# NEWNU32.net
KiCad netlist of a schematic drawn in EAGLE
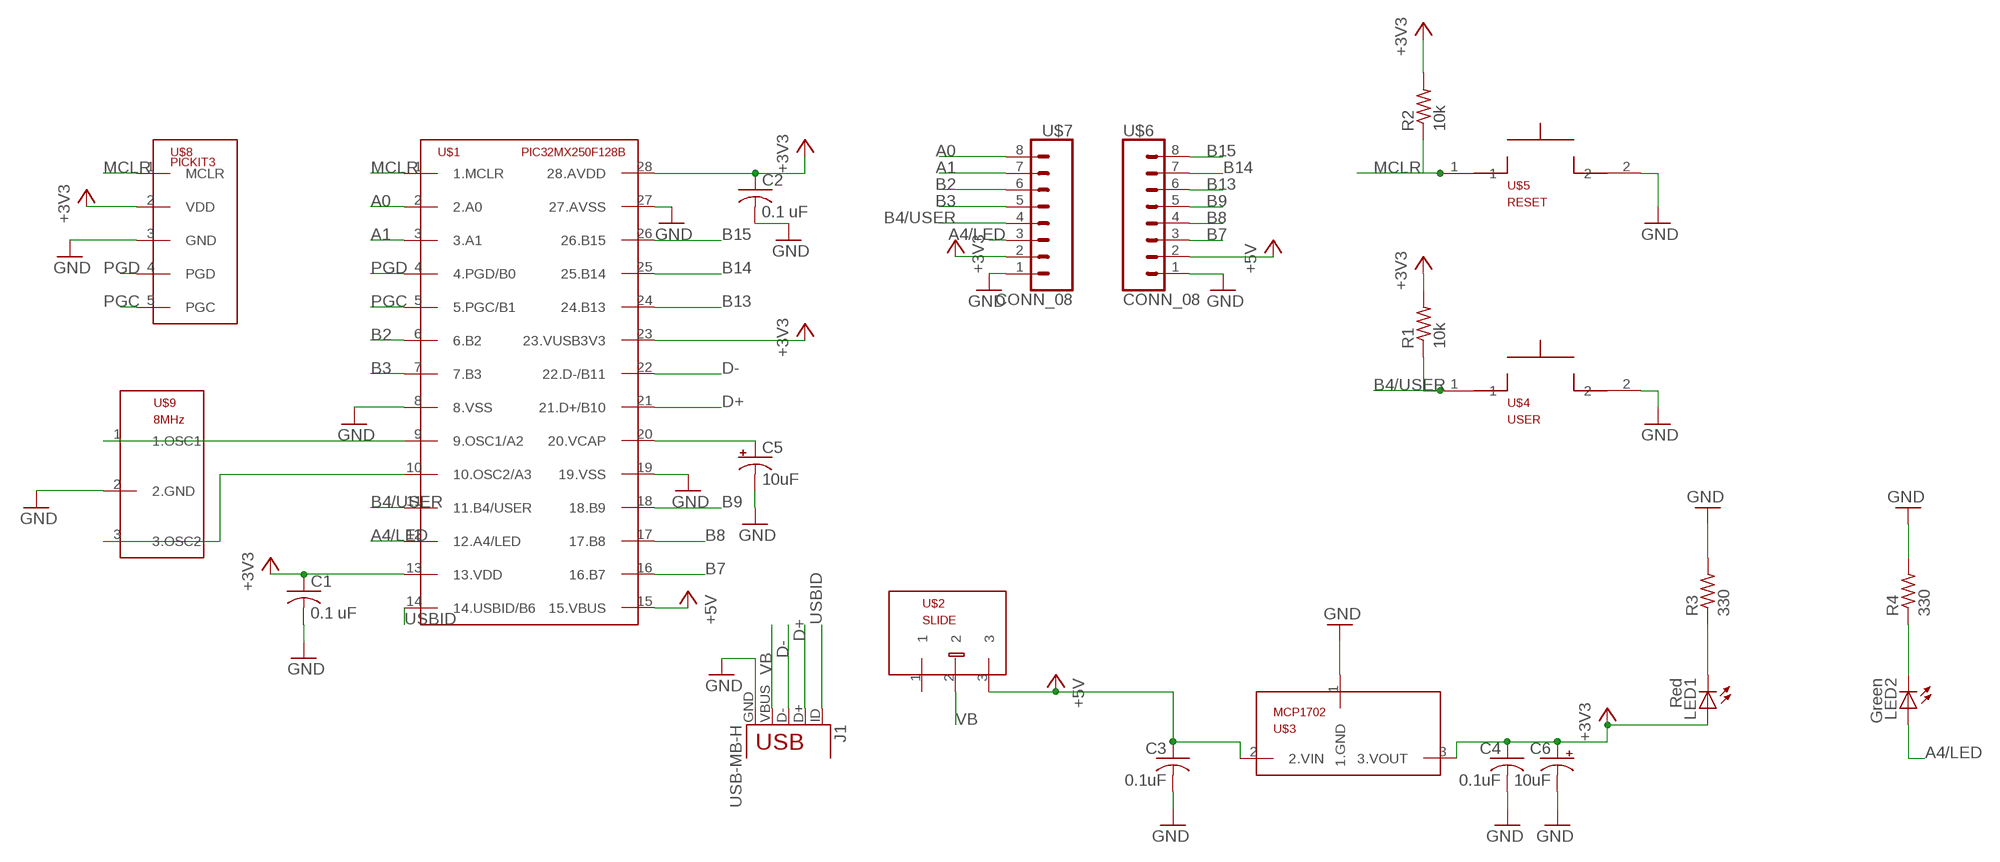
[diagram p0: schematic, sheet 1]

(export (version "E")
  (design (tool "Eeschema 10.0.6"))
  (components
    (comp (ref "C1")
      (value "0.1 uF")
      (footprint "eagle-import:C025-025X050")
      (libsource (lib "eagle-import") (part "C-US025-025X050"))
    )
    (comp (ref "C2")
      (value "0.1 uF")
      (footprint "eagle-import:C025-025X050")
      (libsource (lib "eagle-import") (part "C-US025-025X050"))
    )
    (comp (ref "C3")
      (value "0.1uF")
      (footprint "eagle-import:C025-025X050")
      (libsource (lib "eagle-import") (part "C-US025-025X050"))
    )
    (comp (ref "C4")
      (value "0.1uF")
      (footprint "eagle-import:C025-025X050")
      (libsource (lib "eagle-import") (part "C-US025-025X050"))
    )
    (comp (ref "C5")
      (value "10uF")
      (footprint "eagle-import:B45181B")
      (libsource (lib "eagle-import") (part "CPOL-USB45181B"))
    )
    (comp (ref "C6")
      (value "10uF")
      (footprint "eagle-import:B45181B")
      (libsource (lib "eagle-import") (part "CPOL-USB45181B"))
    )
    (comp (ref "J1")
      (value "USB-MB-H")
      (footprint "eagle-import:USB-MB-H")
      (libsource (lib "eagle-import") (part "USB-MB-H"))
    )
    (comp (ref "LED1")
      (value "Red")
      (footprint "eagle-import:LED3MM")
      (libsource (lib "eagle-import") (part "LED3MM"))
    )
    (comp (ref "LED2")
      (value "Green")
      (footprint "eagle-import:LED3MM")
      (libsource (lib "eagle-import") (part "LED3MM"))
    )
    (comp (ref "R1")
      (value "10k")
      (footprint "eagle-import:0207_10")
      (libsource (lib "eagle-import") (part "R-US_0207/10"))
    )
    (comp (ref "R2")
      (value "10k")
      (footprint "eagle-import:0207_10")
      (libsource (lib "eagle-import") (part "R-US_0207/10"))
    )
    (comp (ref "R3")
      (value "330")
      (footprint "eagle-import:0207_10")
      (libsource (lib "eagle-import") (part "R-US_0207/10"))
    )
    (comp (ref "R4")
      (value "330")
      (footprint "eagle-import:0207_10")
      (libsource (lib "eagle-import") (part "R-US_0207/10"))
    )
    (comp (ref "U$1")
      (value "PIC32MX250F128B")
      (footprint "eagle-import:DIL28-3")
      (libsource (lib "eagle-import") (part "PIC32MX250F128B"))
    )
    (comp (ref "U$2")
      (value "SLIDE")
      (footprint "eagle-import:SLIDE")
      (libsource (lib "eagle-import") (part "SLIDE"))
    )
    (comp (ref "U$3")
      (value "MCP1702")
      (footprint "eagle-import:TO92")
      (libsource (lib "eagle-import") (part "MCP1702"))
    )
    (comp (ref "U$4")
      (value "USER")
      (footprint "eagle-import:PB")
      (libsource (lib "eagle-import") (part "PB"))
    )
    (comp (ref "U$5")
      (value "RESET")
      (footprint "eagle-import:PB")
      (libsource (lib "eagle-import") (part "PB"))
    )
    (comp (ref "U$6")
      (value "CONN_08")
      (footprint "eagle-import:1X08")
      (libsource (lib "eagle-import") (part "CONN_08"))
    )
    (comp (ref "U$7")
      (value "CONN_08")
      (footprint "eagle-import:1X08")
      (libsource (lib "eagle-import") (part "CONN_08"))
    )
    (comp (ref "U$8")
      (value "PICKIT3")
      (footprint "eagle-import:1X05")
      (libsource (lib "eagle-import") (part "PICKIT3"))
    )
    (comp (ref "U$9")
      (value "8MHz")
      (footprint "eagle-import:OSC")
      (libsource (lib "eagle-import") (part "OSC"))
    )
  )
  (nets
    (net (code "1") (name "+3V3") (class "Default")
      (node (ref "C1") (pin "1") (pinfunction "1_1") (pintype "passive"))
      (node (ref "C2") (pin "1") (pinfunction "1_1") (pintype "passive"))
      (node (ref "C4") (pin "1") (pinfunction "1_1") (pintype "passive"))
      (node (ref "C6") (pin "+") (pinfunction "+_+") (pintype "passive"))
      (node (ref "LED1") (pin "A") (pinfunction "A_A") (pintype "passive"))
      (node (ref "R1") (pin "2") (pinfunction "2_2") (pintype "passive"))
      (node (ref "R2") (pin "2") (pinfunction "2_2") (pintype "passive"))
      (node (ref "U$1") (pin "13") (pinfunction "13.VDD_13") (pintype "bidirectional"))
      (node (ref "U$1") (pin "23") (pinfunction "23.VUSB3V3_23") (pintype "bidirectional"))
      (node (ref "U$1") (pin "28") (pinfunction "28.AVDD_28") (pintype "bidirectional"))
      (node (ref "U$3") (pin "3") (pinfunction "3.VOUT_3") (pintype "bidirectional"))
      (node (ref "U$7") (pin "2") (pinfunction "2_2") (pintype "passive"))
      (node (ref "U$8") (pin "2") (pinfunction "VDD_2") (pintype "bidirectional"))
    )
    (net (code "2") (name "+5V") (class "Default")
      (node (ref "C3") (pin "1") (pinfunction "1_1") (pintype "passive"))
      (node (ref "U$1") (pin "15") (pinfunction "15.VBUS_15") (pintype "bidirectional"))
      (node (ref "U$2") (pin "3") (pinfunction "3_3") (pintype "bidirectional"))
      (node (ref "U$3") (pin "2") (pinfunction "2.VIN_2") (pintype "bidirectional"))
      (node (ref "U$6") (pin "2") (pinfunction "2_2") (pintype "passive"))
    )
    (net (code "3") (name "/A0") (class "Default")
      (node (ref "U$1") (pin "2") (pinfunction "2.A0_2") (pintype "bidirectional"))
      (node (ref "U$7") (pin "8") (pinfunction "8_8") (pintype "passive"))
    )
    (net (code "4") (name "/A1") (class "Default")
      (node (ref "U$1") (pin "3") (pinfunction "3.A1_3") (pintype "bidirectional"))
      (node (ref "U$7") (pin "7") (pinfunction "7_7") (pintype "passive"))
    )
    (net (code "5") (name "/A4{slash}LED") (class "Default")
      (node (ref "LED2") (pin "A") (pinfunction "A_A") (pintype "passive"))
      (node (ref "U$1") (pin "12") (pinfunction "12.A4/LED_12") (pintype "bidirectional"))
      (node (ref "U$7") (pin "3") (pinfunction "3_3") (pintype "passive"))
    )
    (net (code "6") (name "/B2") (class "Default")
      (node (ref "U$1") (pin "6") (pinfunction "6.B2_6") (pintype "bidirectional"))
      (node (ref "U$7") (pin "6") (pinfunction "6_6") (pintype "passive"))
    )
    (net (code "7") (name "/B3") (class "Default")
      (node (ref "U$1") (pin "7") (pinfunction "7.B3_7") (pintype "bidirectional"))
      (node (ref "U$7") (pin "5") (pinfunction "5_5") (pintype "passive"))
    )
    (net (code "8") (name "/B4{slash}USER") (class "Default")
      (node (ref "R1") (pin "1") (pinfunction "1_1") (pintype "passive"))
      (node (ref "U$1") (pin "11") (pinfunction "11.B4/USER_11") (pintype "bidirectional"))
      (node (ref "U$4") (pin "1") (pinfunction "1_1") (pintype "bidirectional"))
      (node (ref "U$7") (pin "4") (pinfunction "4_4") (pintype "passive"))
    )
    (net (code "9") (name "/B7") (class "Default")
      (node (ref "U$1") (pin "16") (pinfunction "16.B7_16") (pintype "bidirectional"))
      (node (ref "U$6") (pin "3") (pinfunction "3_3") (pintype "passive"))
    )
    (net (code "10") (name "/B8") (class "Default")
      (node (ref "U$1") (pin "17") (pinfunction "17.B8_17") (pintype "bidirectional"))
      (node (ref "U$6") (pin "4") (pinfunction "4_4") (pintype "passive"))
    )
    (net (code "11") (name "/B9") (class "Default")
      (node (ref "U$1") (pin "18") (pinfunction "18.B9_18") (pintype "bidirectional"))
      (node (ref "U$6") (pin "5") (pinfunction "5_5") (pintype "passive"))
    )
    (net (code "12") (name "/B13") (class "Default")
      (node (ref "U$1") (pin "24") (pinfunction "24.B13_24") (pintype "bidirectional"))
      (node (ref "U$6") (pin "6") (pinfunction "6_6") (pintype "passive"))
    )
    (net (code "13") (name "/B14") (class "Default")
      (node (ref "U$1") (pin "25") (pinfunction "25.B14_25") (pintype "bidirectional"))
      (node (ref "U$6") (pin "7") (pinfunction "7_7") (pintype "passive"))
    )
    (net (code "14") (name "/B15") (class "Default")
      (node (ref "U$1") (pin "26") (pinfunction "26.B15_26") (pintype "bidirectional"))
      (node (ref "U$6") (pin "8") (pinfunction "8_8") (pintype "passive"))
    )
    (net (code "15") (name "/D+") (class "Default")
      (node (ref "J1") (pin "D+") (pinfunction "D+_D+") (pintype "bidirectional"))
      (node (ref "U$1") (pin "21") (pinfunction "21.D+/B10_21") (pintype "bidirectional"))
    )
    (net (code "16") (name "/D-") (class "Default")
      (node (ref "J1") (pin "D-") (pinfunction "D-_D-") (pintype "bidirectional"))
      (node (ref "U$1") (pin "22") (pinfunction "22.D-/B11_22") (pintype "bidirectional"))
    )
    (net (code "17") (name "/MCLR") (class "Default")
      (node (ref "R2") (pin "1") (pinfunction "1_1") (pintype "passive"))
      (node (ref "U$1") (pin "1") (pinfunction "1.MCLR_1") (pintype "bidirectional"))
      (node (ref "U$5") (pin "1") (pinfunction "1_1") (pintype "bidirectional"))
      (node (ref "U$8") (pin "1") (pinfunction "MCLR_1") (pintype "bidirectional"))
    )
    (net (code "18") (name "/PGC") (class "Default")
      (node (ref "U$1") (pin "5") (pinfunction "5.PGC/B1_5") (pintype "bidirectional"))
      (node (ref "U$8") (pin "5") (pinfunction "PGC_5") (pintype "bidirectional"))
    )
    (net (code "19") (name "/PGD") (class "Default")
      (node (ref "U$1") (pin "4") (pinfunction "4.PGD/B0_4") (pintype "bidirectional"))
      (node (ref "U$8") (pin "4") (pinfunction "PGD_4") (pintype "bidirectional"))
    )
    (net (code "20") (name "/USBID") (class "Default")
      (node (ref "J1") (pin "ID") (pinfunction "ID_ID") (pintype "bidirectional"))
      (node (ref "U$1") (pin "14") (pinfunction "14.USBID/B6_14") (pintype "bidirectional"))
    )
    (net (code "21") (name "/VB") (class "Default")
      (node (ref "J1") (pin "VBUS") (pinfunction "VBUS_VBUS") (pintype "bidirectional"))
      (node (ref "U$2") (pin "2") (pinfunction "2_2") (pintype "bidirectional"))
    )
    (net (code "22") (name "GND") (class "Default")
      (node (ref "C1") (pin "2") (pinfunction "2_2") (pintype "passive"))
      (node (ref "C2") (pin "2") (pinfunction "2_2") (pintype "passive"))
      (node (ref "C3") (pin "2") (pinfunction "2_2") (pintype "passive"))
      (node (ref "C4") (pin "2") (pinfunction "2_2") (pintype "passive"))
      (node (ref "C5") (pin "-") (pinfunction "-_-") (pintype "passive"))
      (node (ref "C6") (pin "-") (pinfunction "-_-") (pintype "passive"))
      (node (ref "J1") (pin "GND") (pinfunction "GND_GND") (pintype "bidirectional"))
      (node (ref "R3") (pin "2") (pinfunction "2_2") (pintype "passive"))
      (node (ref "R4") (pin "2") (pinfunction "2_2") (pintype "passive"))
      (node (ref "U$1") (pin "19") (pinfunction "19.VSS_19") (pintype "bidirectional"))
      (node (ref "U$1") (pin "27") (pinfunction "27.AVSS_27") (pintype "bidirectional"))
      (node (ref "U$1") (pin "8") (pinfunction "8.VSS_8") (pintype "bidirectional"))
      (node (ref "U$3") (pin "1") (pinfunction "1.GND_1") (pintype "bidirectional"))
      (node (ref "U$4") (pin "2") (pinfunction "2_2") (pintype "bidirectional"))
      (node (ref "U$5") (pin "2") (pinfunction "2_2") (pintype "bidirectional"))
      (node (ref "U$6") (pin "1") (pinfunction "1_1") (pintype "passive"))
      (node (ref "U$7") (pin "1") (pinfunction "1_1") (pintype "passive"))
      (node (ref "U$8") (pin "3") (pinfunction "GND_3") (pintype "bidirectional"))
      (node (ref "U$9") (pin "2") (pinfunction "2.GND_2") (pintype "bidirectional"))
    )
    (net (code "23") (name "Net-(LED1-C)") (class "Default")
      (node (ref "LED1") (pin "K") (pinfunction "C_K") (pintype "passive"))
      (node (ref "R3") (pin "1") (pinfunction "1_1") (pintype "passive"))
    )
    (net (code "24") (name "Net-(LED2-C)") (class "Default")
      (node (ref "LED2") (pin "K") (pinfunction "C_K") (pintype "passive"))
      (node (ref "R4") (pin "1") (pinfunction "1_1") (pintype "passive"))
    )
    (net (code "25") (name "Net-(U$1-9.OSC1{slash}A2)") (class "Default")
      (node (ref "U$1") (pin "9") (pinfunction "9.OSC1/A2_9") (pintype "bidirectional"))
      (node (ref "U$9") (pin "1") (pinfunction "1.OSC1_1") (pintype "bidirectional"))
    )
    (net (code "26") (name "Net-(U$1-10.OSC2{slash}A3)") (class "Default")
      (node (ref "U$1") (pin "10") (pinfunction "10.OSC2/A3_10") (pintype "bidirectional"))
      (node (ref "U$9") (pin "3") (pinfunction "3.OSC2_3") (pintype "bidirectional"))
    )
    (net (code "27") (name "Net-(U$1-20.VCAP)") (class "Default")
      (node (ref "C5") (pin "+") (pinfunction "+_+") (pintype "passive"))
      (node (ref "U$1") (pin "20") (pinfunction "20.VCAP_20") (pintype "bidirectional"))
    )
    (net (code "28") (name "unconnected-(U$2-Pad1)") (class "Default")
      (node (ref "U$2") (pin "1") (pinfunction "1_1") (pintype "bidirectional"))
    )
  )
)
